# Sheet1.net
KiCad netlist of a schematic drawn in Altium Designer
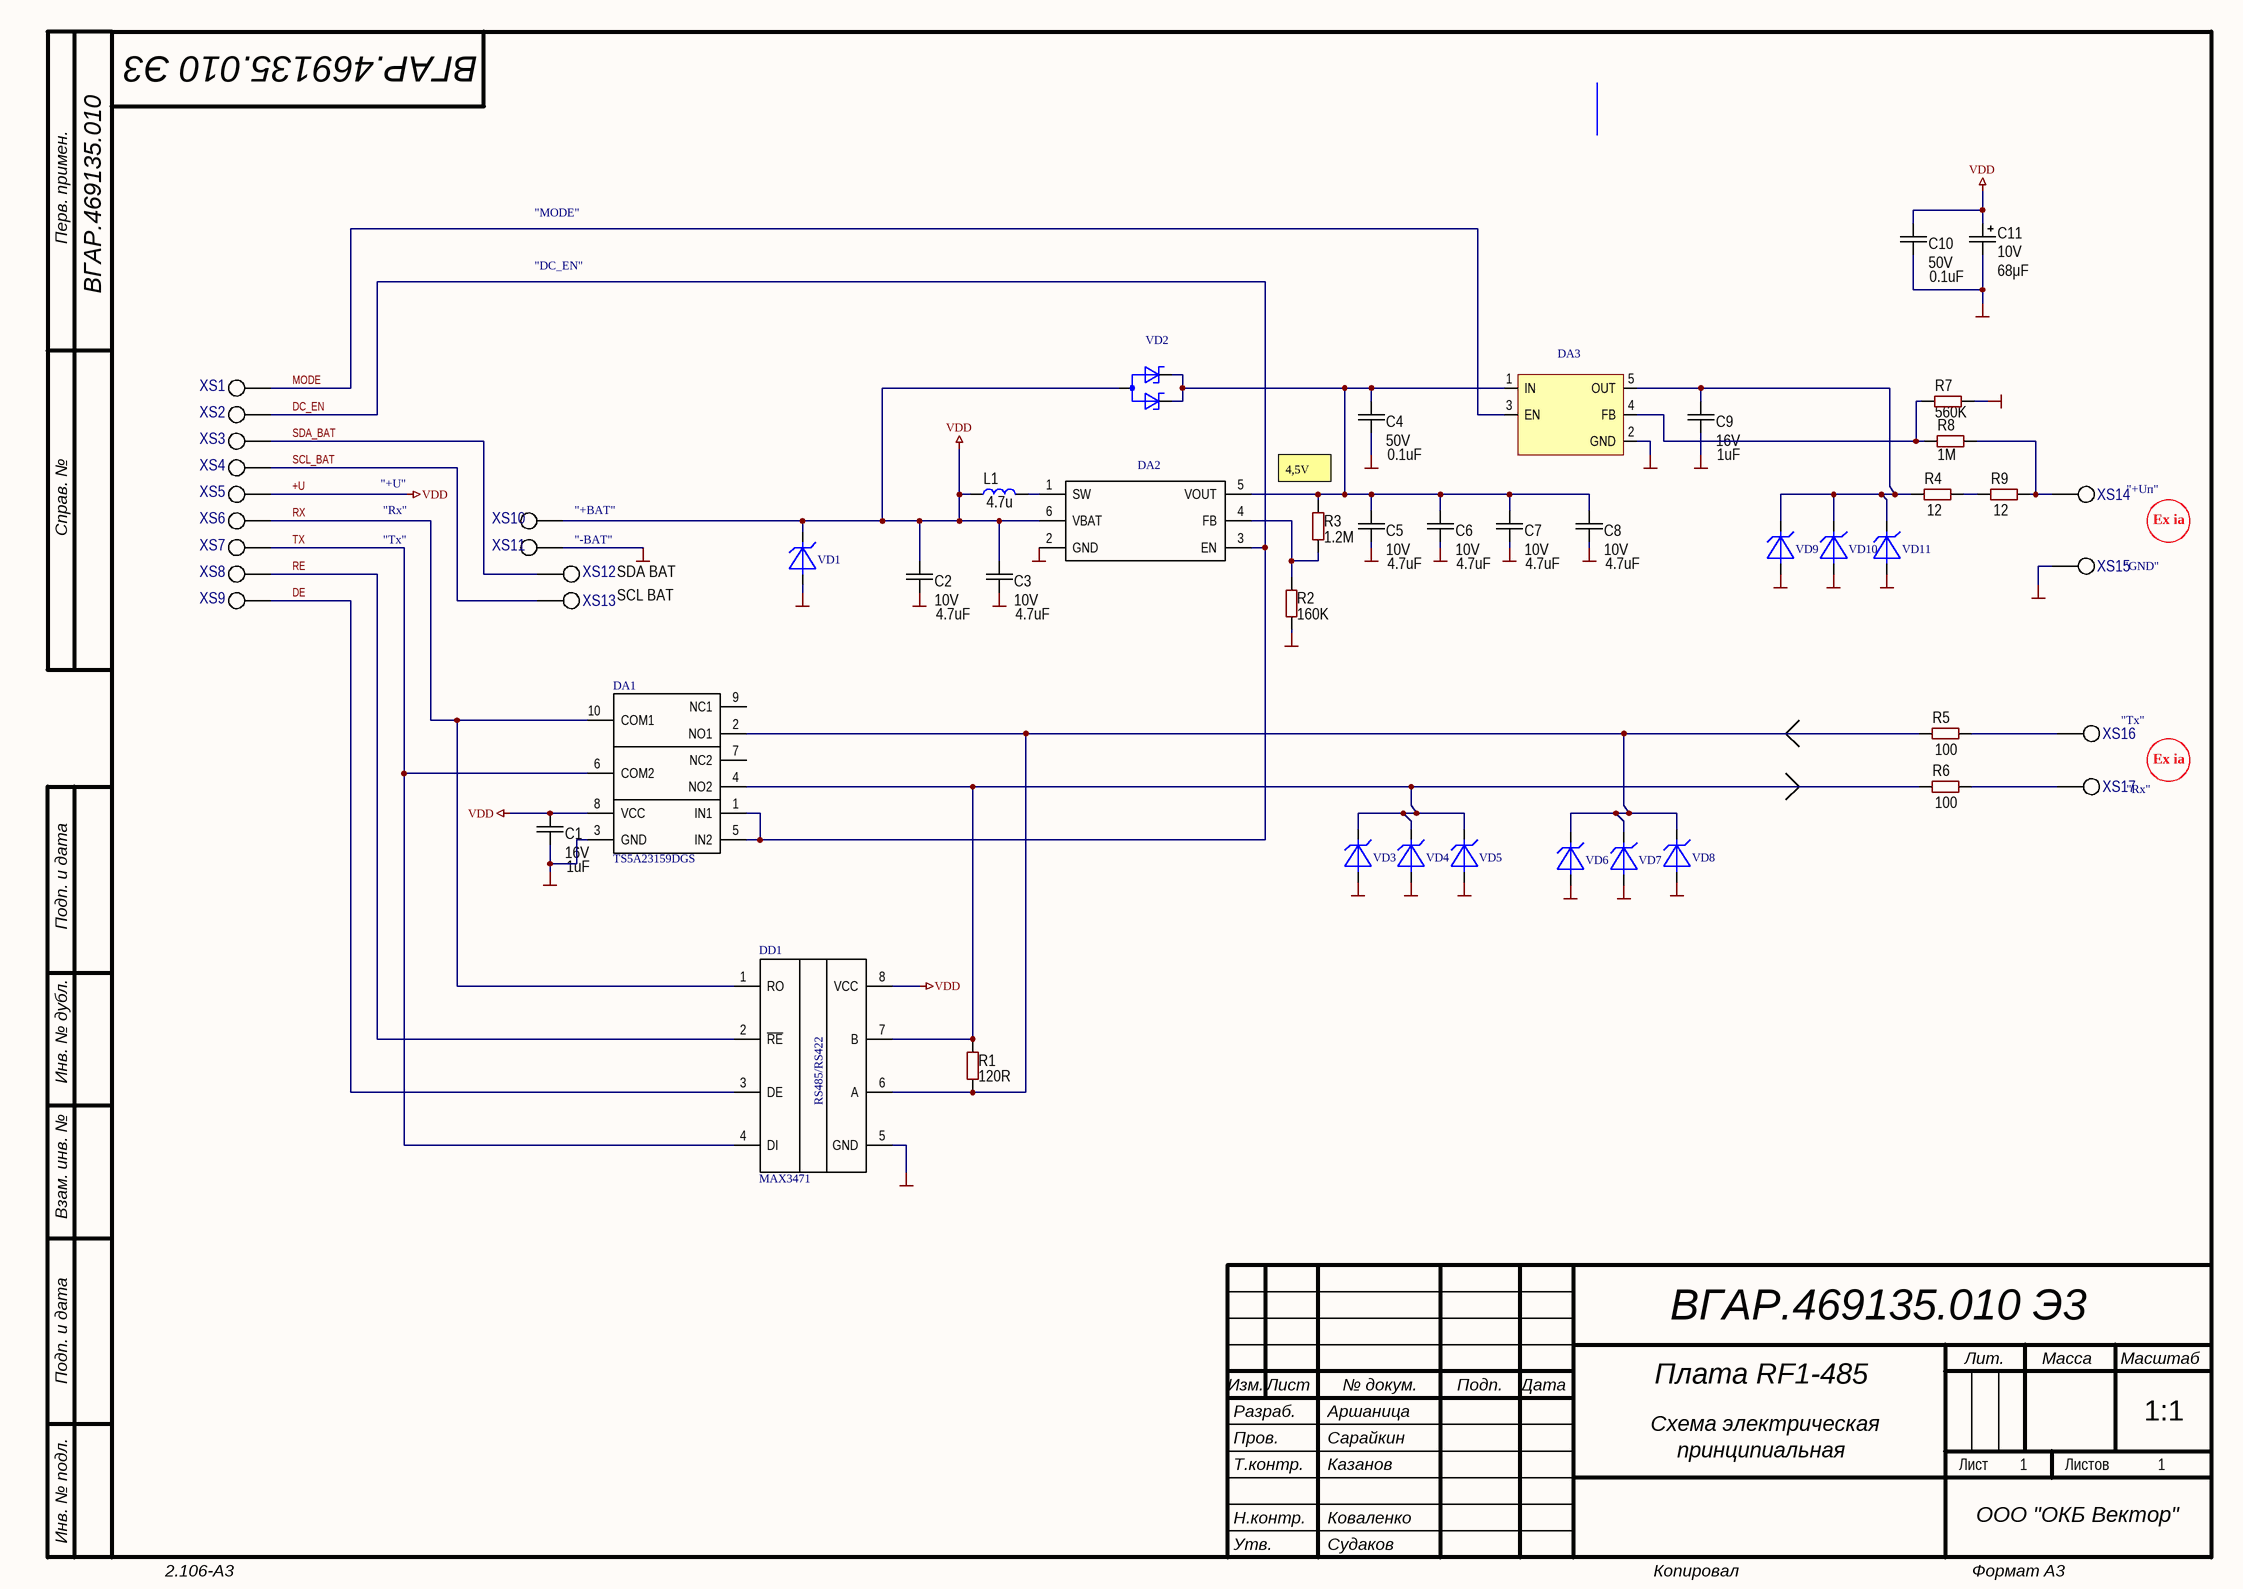
[diagram p0: Sheet1.SchDoc]

(export (version "E")
  (design (tool "Eeschema 10.0.6"))
  (components
    (comp (ref "C1")
      (value "1uF")
      (footprint "CAP: 0603")
      (fields
        (field (name "MANUFACTURER") "Yageo")
        (field (name "PARTNUMBER") "CC0603KRX7R7BB104")
        (field (name "VALUEMANUFACTURERPARTNUMBER") "Ceramic capacitor, 1uF, X7R, ±10%, 16V, 0603, -55...+125°C")
        (field (name "VOLTAGE") "16V")
      )
      (libsource (lib "capacitor") (part "Ceramic_0603"))
    )
    (comp (ref "C2")
      (value "4.7uF")
      (footprint "CAP: 0603")
      (fields
        (field (name "MANUFACTURER") "Yageo")
        (field (name "PARTNUMBER") "CC0603KRX7R7BB104")
        (field (name "VALUEMANUFACTURERPARTNUMBER") "Ceramic capacitor, 4.7uF, X7R, ±10%, 10V, 0603, -55...+125°C")
        (field (name "VOLTAGE") "10V")
      )
      (libsource (lib "capacitor") (part "Ceramic_0603"))
    )
    (comp (ref "C3")
      (value "4.7uF")
      (footprint "CAP: 0603")
      (fields
        (field (name "MANUFACTURER") "Yageo")
        (field (name "PARTNUMBER") "CC0603KRX7R7BB104")
        (field (name "VALUEMANUFACTURERPARTNUMBER") "Ceramic capacitor, 4.7uF, X7R, ±10%, 10V, 0603, -55...+125°C")
        (field (name "VOLTAGE") "10V")
      )
      (libsource (lib "capacitor") (part "Ceramic_0603"))
    )
    (comp (ref "C4")
      (value "0.1uF")
      (footprint "CAP: 0603")
      (fields
        (field (name "MANUFACTURER") "Yageo")
        (field (name "PARTNUMBER") "CC0603KRX7R7BB104")
        (field (name "VALUEMANUFACTURERPARTNUMBER") "Ceramic capacitor, 0.1uF, X7R, ±10%, 50V, 0603, -55...+125°C")
        (field (name "VOLTAGE") "50V")
      )
      (libsource (lib "capacitor") (part "Ceramic_0603"))
    )
    (comp (ref "C5")
      (value "4.7uF")
      (footprint "CAP: 0603")
      (fields
        (field (name "MANUFACTURER") "Yageo")
        (field (name "PARTNUMBER") "CC0603KRX7R7BB104")
        (field (name "VALUEMANUFACTURERPARTNUMBER") "Ceramic capacitor, 4.7uF, X7R, ±10%, 10V, 0603, -55...+125°C")
        (field (name "VOLTAGE") "10V")
      )
      (libsource (lib "capacitor") (part "Ceramic_0603"))
    )
    (comp (ref "C6")
      (value "4.7uF")
      (footprint "CAP: 0603")
      (fields
        (field (name "MANUFACTURER") "Yageo")
        (field (name "PARTNUMBER") "CC0603KRX7R7BB104")
        (field (name "VALUEMANUFACTURERPARTNUMBER") "Ceramic capacitor, 4.7uF, X7R, ±10%, 10V, 0603, -55...+125°C")
        (field (name "VOLTAGE") "10V")
      )
      (libsource (lib "capacitor") (part "Ceramic_0603"))
    )
    (comp (ref "C7")
      (value "4.7uF")
      (footprint "CAP: 0603")
      (fields
        (field (name "MANUFACTURER") "Yageo")
        (field (name "PARTNUMBER") "CC0603KRX7R7BB104")
        (field (name "VALUEMANUFACTURERPARTNUMBER") "Ceramic capacitor, 4.7uF, X7R, ±10%, 10V, 0603, -55...+125°C")
        (field (name "VOLTAGE") "10V")
      )
      (libsource (lib "capacitor") (part "Ceramic_0603"))
    )
    (comp (ref "C8")
      (value "4.7uF")
      (footprint "CAP: 0603")
      (fields
        (field (name "MANUFACTURER") "Yageo")
        (field (name "PARTNUMBER") "CC0603KRX7R7BB104")
        (field (name "VALUEMANUFACTURERPARTNUMBER") "Ceramic capacitor, 4.7uF, X7R, ±10%, 10V, 0603, -55...+125°C")
        (field (name "VOLTAGE") "10V")
      )
      (libsource (lib "capacitor") (part "Ceramic_0603"))
    )
    (comp (ref "C9")
      (value "1uF")
      (footprint "CAP: 0603")
      (fields
        (field (name "MANUFACTURER") "Yageo")
        (field (name "PARTNUMBER") "CC0603KRX7R7BB104")
        (field (name "VALUEMANUFACTURERPARTNUMBER") "Ceramic capacitor, 1uF, X7R, ±10%, 16V, 0603, -55...+125°C")
        (field (name "VOLTAGE") "16V")
      )
      (libsource (lib "capacitor") (part "Ceramic_0603"))
    )
    (comp (ref "C10")
      (value "0.1uF")
      (footprint "CAP: 0603")
      (fields
        (field (name "MANUFACTURER") "Yageo")
        (field (name "PARTNUMBER") "CC0603KRX7R7BB104")
        (field (name "VALUEMANUFACTURERPARTNUMBER") "Ceramic capacitor, 0.1uF, X7R, ±10%, 50V, 0603, -55...+125°C")
        (field (name "VOLTAGE") "50V")
      )
      (libsource (lib "") (part "Ceramic_0603_1"))
    )
    (comp (ref "C11")
      (value "68μF")
      (footprint "CAP: TANTAL-B")
      (fields
        (field (name "MANUFACTURER") "AVX")
        (field (name "PARTNUMBER") "F930J227KBA")
        (field (name "VALUEMANUFACTURERPARTNUMBER") "Tantalum capacitor, 68μF, 10V, ±10%, 1.2Ohm, case B (3528), -55...+125°C")
        (field (name "VOLTAGE") "10V")
      )
      (libsource (lib "capacitor") (part "Tantal_B"))
    )
    (comp (ref "DA1")
      (value "TS5A23159DGS")
      (footprint "VSSSOP-10 - TI")
      (description "Микросхема")
      (fields (field (name "MANUFACTURER") "Texas Instruments"))
      (libsource (lib "TI Analog Switch") (part "TS5A23159DGS"))
    )
    (comp (ref "DA2")
      (value "TPS6107x")
      (footprint "SOT23-6")
      (description "Микросхема")
      (fields (field (name "MANUFACTURER") "Texas Instruments"))
      (libsource (lib "TI Power Mgt Switchmode Regulator") (part "TPS61070"))
    )
    (comp (ref "DA3")
      (value "TPS78001DDC")
      (footprint "SOT23-5")
      (description "Микросхема")
      (fields
        (field (name "MANUFACTURER") "Texas Instruments")
        (field (name "PART NUMBER") "TPS780270200DDCT")
      )
      (libsource (lib "TI LDO") (part "TPS78001DDC"))
    )
    (comp (ref "DD1")
      (value "MAX3471")
      (footprint "MSOP-8")
      (description "RS-485/RS422Half-Duplex,  Differential Transceiver for Battery-Powered Systems")
      (fields (field (name "MANUFACTURER") "MAXIM"))
      (libsource (lib "Maxim Interface") (part "MAX3471"))
    )
    (comp (ref "L1")
      (value "4.7u")
      (footprint "IND: CDRH4D28NP")
      (fields (field (name "Comment") "CDRH4D"))
      (libsource (lib "inductor") (part "CDRH4D28NP"))
    )
    (comp (ref "R1")
      (value "120R")
      (footprint "RES: 0603")
      (fields
        (field (name "MANUFACTURER") "Yageo")
        (field (name "PARTNUMBER") "RC0603JR-07100RL")
        (field (name "VALUEMANUFACTURERPARTNUMBER") "Resistor film, 120R, ±5%, 0603, 0.1W, -55...+125°C")
      )
      (libsource (lib "resistor") (part "Resistor_0603"))
    )
    (comp (ref "R2")
      (value "160K")
      (footprint "RES: 0603")
      (fields
        (field (name "MANUFACTURER") "Yageo")
        (field (name "PARTNUMBER") "RC0603JR-07100RL")
        (field (name "VALUEMANUFACTURERPARTNUMBER") "Resistor film, 160K, ±5%, 0603, 0.1W, -55...+125°C")
      )
      (libsource (lib "resistor") (part "Resistor_0603"))
    )
    (comp (ref "R3")
      (value "1.2M")
      (footprint "RES: 0603")
      (fields
        (field (name "MANUFACTURER") "Yageo")
        (field (name "PARTNUMBER") "RC0603JR-07100RL")
        (field (name "VALUEMANUFACTURERPARTNUMBER") "Resistor film, 1.2M, ±5%, 0603, 0.1W, -55...+125°C")
      )
      (libsource (lib "resistor") (part "Resistor_0603"))
    )
    (comp (ref "R4")
      (value "12")
      (footprint "RES: 2512")
      (fields
        (field (name "MANUFACTURER") "Yageo")
        (field (name "PARTNUMBER") "RC2512JK-07100RL")
        (field (name "VALUEMANUFACTURERPARTNUMBER") "Resistor film, 12, ±5%, 2512, 1W, -55...+125°C")
      )
      (libsource (lib "resistor") (part "Resistor_2512"))
    )
    (comp (ref "R5")
      (value "100")
      (footprint "RES: 2512")
      (fields
        (field (name "MANUFACTURER") "Yageo")
        (field (name "PARTNUMBER") "RC2512JK-07100RL")
        (field (name "VALUEMANUFACTURERPARTNUMBER") "Resistor film, 100, ±5%, 2512, 1W, -55...+125°C")
      )
      (libsource (lib "resistor") (part "Resistor_2512"))
    )
    (comp (ref "R6")
      (value "100")
      (footprint "RES: 2512")
      (fields
        (field (name "MANUFACTURER") "Yageo")
        (field (name "PARTNUMBER") "RC2512JK-07100RL")
        (field (name "VALUEMANUFACTURERPARTNUMBER") "Resistor film, 100, ±5%, 2512, 1W, -55...+125°C")
      )
      (libsource (lib "resistor") (part "Resistor_2512"))
    )
    (comp (ref "R7")
      (value "560K")
      (footprint "RES: 0603")
      (fields
        (field (name "MANUFACTURER") "Yageo")
        (field (name "PARTNUMBER") "RC0603JR-07100RL")
        (field (name "VALUEMANUFACTURERPARTNUMBER") "Resistor film, 560K, ±5%, 0603, 0.1W, -55...+125°C")
      )
      (libsource (lib "") (part "Resistor_0603_1"))
    )
    (comp (ref "R8")
      (value "1M")
      (footprint "RES: 0603")
      (fields
        (field (name "MANUFACTURER") "Yageo")
        (field (name "PARTNUMBER") "RC0603JR-07100RL")
        (field (name "VALUEMANUFACTURERPARTNUMBER") "Resistor film, 1M, ±5%, 0603, 0.1W, -55...+125°C")
      )
      (libsource (lib "") (part "Resistor_0603_1"))
    )
    (comp (ref "R9")
      (value "12")
      (footprint "RES: 2512")
      (fields
        (field (name "MANUFACTURER") "Yageo")
        (field (name "PARTNUMBER") "RC2512JK-07100RL")
        (field (name "VALUEMANUFACTURERPARTNUMBER") "Resistor film, 12, ±5%, 2512, 1W, -55...+125°C")
      )
      (libsource (lib "resistor") (part "Resistor_2512"))
    )
    (comp (ref "VD1")
      (value "SM2T")
      (footprint "DO216-AA")
      (description "TVS Диод")
      (fields (field (name "MANUFACTURER") "ST Microelectronics"))
      (libsource (lib "ST Protection Diodes") (part "SM2T"))
    )
    (comp (ref "VD2")
      (value "BAT54AW")
      (footprint "SC-70")
      (description "Сборка диодная")
      (fields (field (name "MANUFACTURER") "NXP") (field (name "REPLACEMENTPART1PARTNUMBER") "BAT54AWT1G"))
      (libsource (lib "NXP Diodes") (part "BAT54AW"))
    )
    (comp (ref "VD3")
      (value "SM2T")
      (footprint "DO216-AA")
      (description "TVS Диод")
      (fields (field (name "MANUFACTURER") "ST Microelectronics"))
      (libsource (lib "ST Protection Diodes") (part "SM2T"))
    )
    (comp (ref "VD4")
      (value "SM2T")
      (footprint "DO216-AA")
      (description "TVS Диод")
      (fields (field (name "MANUFACTURER") "ST Microelectronics"))
      (libsource (lib "ST Protection Diodes") (part "SM2T"))
    )
    (comp (ref "VD5")
      (value "SM2T")
      (footprint "DO216-AA")
      (description "TVS Диод")
      (fields (field (name "MANUFACTURER") "ST Microelectronics"))
      (libsource (lib "ST Protection Diodes") (part "SM2T"))
    )
    (comp (ref "VD6")
      (value "SM2T")
      (footprint "DO216-AA")
      (description "TVS Диод")
      (fields (field (name "MANUFACTURER") "ST Microelectronics"))
      (libsource (lib "ST Protection Diodes") (part "SM2T"))
    )
    (comp (ref "VD7")
      (value "SM2T")
      (footprint "DO216-AA")
      (description "TVS Диод")
      (fields (field (name "MANUFACTURER") "ST Microelectronics"))
      (libsource (lib "ST Protection Diodes") (part "SM2T"))
    )
    (comp (ref "VD8")
      (value "SM2T")
      (footprint "DO216-AA")
      (description "TVS Диод")
      (fields (field (name "MANUFACTURER") "ST Microelectronics"))
      (libsource (lib "ST Protection Diodes") (part "SM2T"))
    )
    (comp (ref "VD9")
      (value "SM2T")
      (footprint "DO216-AA")
      (description "TVS Диод")
      (fields (field (name "MANUFACTURER") "ST Microelectronics"))
      (libsource (lib "ST Protection Diodes") (part "SM2T"))
    )
    (comp (ref "VD10")
      (value "SM2T")
      (footprint "DO216-AA")
      (description "TVS Диод")
      (fields (field (name "MANUFACTURER") "ST Microelectronics"))
      (libsource (lib "ST Protection Diodes") (part "SM2T"))
    )
    (comp (ref "VD11")
      (value "SM2T")
      (footprint "DO216-AA")
      (description "TVS Диод")
      (fields (field (name "MANUFACTURER") "ST Microelectronics"))
      (libsource (lib "ST Protection Diodes") (part "SM2T"))
    )
    (comp (ref "XS1")
      (value "Testpoint_HS1mm")
      (footprint "TestPoint(without 3D)")
      (libsource (lib "connector") (part "Testpoint_HS1mm"))
    )
    (comp (ref "XS2")
      (value "Testpoint_HS1mm")
      (footprint "TestPoint(without 3D)")
      (libsource (lib "connector") (part "Testpoint_HS1mm"))
    )
    (comp (ref "XS3")
      (value "Testpoint_HS1mm")
      (footprint "TestPoint(without 3D)")
      (libsource (lib "connector") (part "Testpoint_HS1mm"))
    )
    (comp (ref "XS4")
      (value "Testpoint_HS1mm")
      (footprint "TestPoint(without 3D)")
      (libsource (lib "connector") (part "Testpoint_HS1mm"))
    )
    (comp (ref "XS5")
      (value "Testpoint_HS1mm")
      (footprint "TestPoint(without 3D)")
      (libsource (lib "connector") (part "Testpoint_HS1mm"))
    )
    (comp (ref "XS6")
      (value "Testpoint_HS1mm")
      (footprint "TestPoint(without 3D)")
      (libsource (lib "connector") (part "Testpoint_HS1mm"))
    )
    (comp (ref "XS7")
      (value "Testpoint_HS1mm")
      (footprint "TestPoint(without 3D)")
      (libsource (lib "connector") (part "Testpoint_HS1mm"))
    )
    (comp (ref "XS8")
      (value "Testpoint_HS1mm")
      (footprint "TestPoint(without 3D)")
      (libsource (lib "connector") (part "Testpoint_HS1mm"))
    )
    (comp (ref "XS9")
      (value "Testpoint_HS1mm")
      (footprint "TestPoint(without 3D)")
      (libsource (lib "connector") (part "Testpoint_HS1mm"))
    )
    (comp (ref "XS10")
      (value "Testpoint_HS1mm")
      (footprint "TestPoint(without 3D)")
      (libsource (lib "connector") (part "Testpoint_HS1mm"))
    )
    (comp (ref "XS11")
      (value "Testpoint_HS1mm")
      (footprint "TestPoint(without 3D)")
      (libsource (lib "connector") (part "Testpoint_HS1mm"))
    )
    (comp (ref "XS12")
      (value "Testpoint_HS1mm")
      (footprint "TestPoint(without 3D)")
      (libsource (lib "connector") (part "Testpoint_HS1mm"))
    )
    (comp (ref "XS13")
      (value "Testpoint_HS1mm")
      (footprint "TestPoint(without 3D)")
      (libsource (lib "connector") (part "Testpoint_HS1mm"))
    )
    (comp (ref "XS14")
      (value "Testpoint_HS1mm")
      (footprint "TestPoint(without 3D)")
      (libsource (lib "connector") (part "Testpoint_HS1mm"))
    )
    (comp (ref "XS15")
      (value "Testpoint_HS1mm")
      (footprint "TestPoint(without 3D)")
      (libsource (lib "connector") (part "Testpoint_HS1mm"))
    )
    (comp (ref "XS16")
      (value "Testpoint_HS1mm")
      (footprint "TestPoint(without 3D)")
      (libsource (lib "connector") (part "Testpoint_HS1mm"))
    )
    (comp (ref "XS17")
      (value "Testpoint_HS1mm")
      (footprint "TestPoint(without 3D)")
      (libsource (lib "connector") (part "Testpoint_HS1mm"))
    )
  )
  (nets
    (net (code "1") (name "/DC_EN") (class "Default")
      (node (ref "DA1") (pin "1") (pinfunction "IN1_1") (pintype "passive"))
      (node (ref "DA1") (pin "5") (pinfunction "IN2_5") (pintype "passive"))
      (node (ref "DA2") (pin "3") (pinfunction "EN_3") (pintype "passive"))
      (node (ref "XS2") (pin "1") (pinfunction "1_1") (pintype "passive"))
    )
    (net (code "2") (name "/DE") (class "Default")
      (node (ref "DD1") (pin "3") (pinfunction "DE_3") (pintype "passive"))
      (node (ref "XS9") (pin "1") (pinfunction "1_1") (pintype "passive"))
    )
    (net (code "3") (name "/MODE") (class "Default")
      (node (ref "DA3") (pin "3") (pinfunction "EN_3") (pintype "passive"))
      (node (ref "XS1") (pin "1") (pinfunction "1_1") (pintype "passive"))
    )
    (net (code "4") (name "/RE") (class "Default")
      (node (ref "DD1") (pin "2") (pinfunction "~{RE}_2") (pintype "passive"))
      (node (ref "XS8") (pin "1") (pinfunction "1_1") (pintype "passive"))
    )
    (net (code "5") (name "/RX") (class "Default")
      (node (ref "DA1") (pin "10") (pinfunction "COM1_10") (pintype "passive"))
      (node (ref "DD1") (pin "1") (pinfunction "RO_1") (pintype "passive"))
      (node (ref "XS6") (pin "1") (pinfunction "1_1") (pintype "passive"))
    )
    (net (code "6") (name "/SCL_BAT") (class "Default")
      (node (ref "XS13") (pin "1") (pinfunction "1_1") (pintype "passive"))
      (node (ref "XS4") (pin "1") (pinfunction "1_1") (pintype "passive"))
    )
    (net (code "7") (name "/SDA_BAT") (class "Default")
      (node (ref "XS12") (pin "1") (pinfunction "1_1") (pintype "passive"))
      (node (ref "XS3") (pin "1") (pinfunction "1_1") (pintype "passive"))
    )
    (net (code "8") (name "/TX") (class "Default")
      (node (ref "DA1") (pin "6") (pinfunction "COM2_6") (pintype "passive"))
      (node (ref "DD1") (pin "4") (pinfunction "DI_4") (pintype "passive"))
      (node (ref "XS7") (pin "1") (pinfunction "1_1") (pintype "passive"))
    )
    (net (code "9") (name "GND") (class "Default")
      (node (ref "C1") (pin "1") (pinfunction "1_1") (pintype "passive"))
      (node (ref "C10") (pin "1") (pinfunction "1_1") (pintype "passive"))
      (node (ref "C11") (pin "2") (pinfunction "2_2") (pintype "passive"))
      (node (ref "C2") (pin "1") (pinfunction "1_1") (pintype "passive"))
      (node (ref "C3") (pin "1") (pinfunction "1_1") (pintype "passive"))
      (node (ref "C4") (pin "1") (pinfunction "1_1") (pintype "passive"))
      (node (ref "C5") (pin "1") (pinfunction "1_1") (pintype "passive"))
      (node (ref "C6") (pin "1") (pinfunction "1_1") (pintype "passive"))
      (node (ref "C7") (pin "1") (pinfunction "1_1") (pintype "passive"))
      (node (ref "C8") (pin "1") (pinfunction "1_1") (pintype "passive"))
      (node (ref "C9") (pin "1") (pinfunction "1_1") (pintype "passive"))
      (node (ref "DA1") (pin "3") (pinfunction "GND_3") (pintype "passive"))
      (node (ref "DA2") (pin "2") (pinfunction "GND_2") (pintype "power_in"))
      (node (ref "DA3") (pin "2") (pinfunction "GND_2") (pintype "passive"))
      (node (ref "DD1") (pin "5") (pinfunction "GND_5") (pintype "passive"))
      (node (ref "R2") (pin "1") (pinfunction "1_1") (pintype "passive"))
      (node (ref "R7") (pin "1") (pinfunction "1_1") (pintype "passive"))
      (node (ref "VD1") (pin "2") (pinfunction "A_2") (pintype "passive"))
      (node (ref "VD10") (pin "2") (pinfunction "A_2") (pintype "passive"))
      (node (ref "VD11") (pin "2") (pinfunction "A_2") (pintype "passive"))
      (node (ref "VD3") (pin "2") (pinfunction "A_2") (pintype "passive"))
      (node (ref "VD4") (pin "2") (pinfunction "A_2") (pintype "passive"))
      (node (ref "VD5") (pin "2") (pinfunction "A_2") (pintype "passive"))
      (node (ref "VD6") (pin "2") (pinfunction "A_2") (pintype "passive"))
      (node (ref "VD7") (pin "2") (pinfunction "A_2") (pintype "passive"))
      (node (ref "VD8") (pin "2") (pinfunction "A_2") (pintype "passive"))
      (node (ref "VD9") (pin "2") (pinfunction "A_2") (pintype "passive"))
      (node (ref "XS11") (pin "1") (pinfunction "1_1") (pintype "passive"))
      (node (ref "XS15") (pin "1") (pinfunction "1_1") (pintype "passive"))
    )
    (net (code "10") (name "Net-(DA1-NO1)") (class "Default")
      (node (ref "DA1") (pin "2") (pinfunction "NO1_2") (pintype "passive"))
      (node (ref "DD1") (pin "6") (pinfunction "A_6") (pintype "passive"))
      (node (ref "R1") (pin "1") (pinfunction "1_1") (pintype "passive"))
      (node (ref "R5") (pin "1") (pinfunction "1_1") (pintype "passive"))
      (node (ref "VD6") (pin "1") (pinfunction "C_1") (pintype "passive"))
      (node (ref "VD7") (pin "1") (pinfunction "C_1") (pintype "passive"))
      (node (ref "VD8") (pin "1") (pinfunction "C_1") (pintype "passive"))
    )
    (net (code "11") (name "Net-(DA1-NO2)") (class "Default")
      (node (ref "DA1") (pin "4") (pinfunction "NO2_4") (pintype "passive"))
      (node (ref "DD1") (pin "7") (pinfunction "B_7") (pintype "passive"))
      (node (ref "R1") (pin "2") (pinfunction "2_2") (pintype "passive"))
      (node (ref "R6") (pin "1") (pinfunction "1_1") (pintype "passive"))
      (node (ref "VD3") (pin "1") (pinfunction "C_1") (pintype "passive"))
      (node (ref "VD4") (pin "1") (pinfunction "C_1") (pintype "passive"))
      (node (ref "VD5") (pin "1") (pinfunction "C_1") (pintype "passive"))
    )
    (net (code "12") (name "Net-(DA2-FB)") (class "Default")
      (node (ref "DA2") (pin "4") (pinfunction "FB_4") (pintype "passive"))
      (node (ref "R2") (pin "2") (pinfunction "2_2") (pintype "passive"))
      (node (ref "R3") (pin "1") (pinfunction "1_1") (pintype "passive"))
    )
    (net (code "13") (name "Net-(DA2-SW)") (class "Default")
      (node (ref "DA2") (pin "1") (pinfunction "SW_1") (pintype "power_in"))
      (node (ref "L1") (pin "2") (pinfunction "2_2") (pintype "passive"))
    )
    (net (code "14") (name "Net-(DA2-VOUT)") (class "Default")
      (node (ref "C4") (pin "2") (pinfunction "2_2") (pintype "passive"))
      (node (ref "C5") (pin "2") (pinfunction "2_2") (pintype "passive"))
      (node (ref "C6") (pin "2") (pinfunction "2_2") (pintype "passive"))
      (node (ref "C7") (pin "2") (pinfunction "2_2") (pintype "passive"))
      (node (ref "C8") (pin "2") (pinfunction "2_2") (pintype "passive"))
      (node (ref "DA2") (pin "5") (pinfunction "VOUT_5") (pintype "power_in"))
      (node (ref "DA3") (pin "1") (pinfunction "IN_1") (pintype "passive"))
      (node (ref "R3") (pin "2") (pinfunction "2_2") (pintype "passive"))
      (node (ref "VD2") (pin "1") (pinfunction "C_1") (pintype "passive"))
      (node (ref "VD2") (pin "2") (pinfunction "C_2") (pintype "passive"))
    )
    (net (code "15") (name "Net-(DA3-FB)") (class "Default")
      (node (ref "DA3") (pin "4") (pinfunction "FB_4") (pintype "passive"))
      (node (ref "R7") (pin "2") (pinfunction "2_2") (pintype "passive"))
      (node (ref "R8") (pin "2") (pinfunction "2_2") (pintype "passive"))
    )
    (net (code "16") (name "Net-(DA3-OUT)") (class "Default")
      (node (ref "C9") (pin "2") (pinfunction "2_2") (pintype "passive"))
      (node (ref "DA3") (pin "5") (pinfunction "OUT_5") (pintype "passive"))
      (node (ref "R4") (pin "1") (pinfunction "1_1") (pintype "passive"))
      (node (ref "VD10") (pin "1") (pinfunction "C_1") (pintype "passive"))
      (node (ref "VD11") (pin "1") (pinfunction "C_1") (pintype "passive"))
      (node (ref "VD9") (pin "1") (pinfunction "C_1") (pintype "passive"))
    )
    (net (code "17") (name "Net-(R4-Pad2)") (class "Default")
      (node (ref "R4") (pin "2") (pinfunction "2_2") (pintype "passive"))
      (node (ref "R9") (pin "1") (pinfunction "1_1") (pintype "passive"))
    )
    (net (code "18") (name "Net-(R5-Pad2)") (class "Default")
      (node (ref "R5") (pin "2") (pinfunction "2_2") (pintype "passive"))
      (node (ref "XS16") (pin "1") (pinfunction "1_1") (pintype "passive"))
    )
    (net (code "19") (name "Net-(R6-Pad2)") (class "Default")
      (node (ref "R6") (pin "2") (pinfunction "2_2") (pintype "passive"))
      (node (ref "XS17") (pin "1") (pinfunction "1_1") (pintype "passive"))
    )
    (net (code "20") (name "Net-(R8-Pad1)") (class "Default")
      (node (ref "R8") (pin "1") (pinfunction "1_1") (pintype "passive"))
      (node (ref "R9") (pin "2") (pinfunction "2_2") (pintype "passive"))
      (node (ref "XS14") (pin "1") (pinfunction "1_1") (pintype "passive"))
    )
    (net (code "21") (name "VDD") (class "Default")
      (node (ref "C1") (pin "2") (pinfunction "2_2") (pintype "passive"))
      (node (ref "C10") (pin "2") (pinfunction "2_2") (pintype "passive"))
      (node (ref "C11") (pin "1") (pinfunction "1_1") (pintype "passive"))
      (node (ref "C2") (pin "2") (pinfunction "2_2") (pintype "passive"))
      (node (ref "C3") (pin "2") (pinfunction "2_2") (pintype "passive"))
      (node (ref "DA1") (pin "8") (pinfunction "VCC_8") (pintype "passive"))
      (node (ref "DA2") (pin "6") (pinfunction "VBAT_6") (pintype "power_in"))
      (node (ref "DD1") (pin "8") (pinfunction "VCC_8") (pintype "passive"))
      (node (ref "L1") (pin "1") (pinfunction "1_1") (pintype "passive"))
      (node (ref "VD1") (pin "1") (pinfunction "C_1") (pintype "passive"))
      (node (ref "VD2") (pin "3") (pinfunction "OA_3") (pintype "passive"))
      (node (ref "XS10") (pin "1") (pinfunction "1_1") (pintype "passive"))
      (node (ref "XS5") (pin "1") (pinfunction "1_1") (pintype "passive"))
    )
    (net (code "22") (name "unconnected-(DA1-NC1-Pad9)") (class "Default")
      (node (ref "DA1") (pin "9") (pinfunction "NC1_9") (pintype "passive"))
    )
    (net (code "23") (name "unconnected-(DA1-NC2-Pad7)") (class "Default")
      (node (ref "DA1") (pin "7") (pinfunction "NC2_7") (pintype "passive"))
    )
  )
)
